# YarnControl_Connect_v1_1.net
KiCad netlist of a schematic drawn in Altium Designer
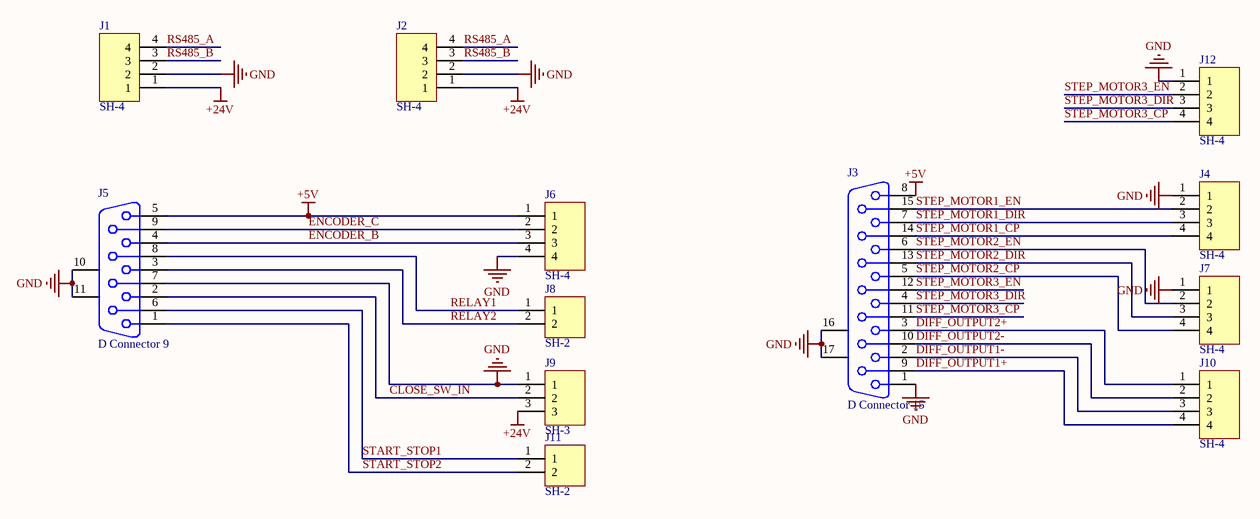
[diagram p0: YarnControl_Connect_v1.1.SchDoc]

(export (version "E")
  (design (tool "Eeschema 10.0.6"))
  (components
    (comp (ref "J1") (value "SH-4") (footprint "PWR") (libsource (lib "") (part "SH-4_1")))
    (comp (ref "J2") (value "SH-4") (footprint "PWR") (libsource (lib "") (part "SH-4_1")))
    (comp (ref "J3")
      (value "D Connector 15")
      (footprint "DSUB1.385-2H15")
      (description "Receptacle Assembly, 15 Position, Right Angle")
      (fields (field (name "PUBLISHER") "Altium Limited"))
      (libsource (lib "Miscellaneous Connectors") (part "D Connector 15"))
    )
    (comp (ref "J4") (value "SH-4") (footprint "PWR") (libsource (lib "Connector") (part "SH-4")))
    (comp (ref "J5")
      (value "D Connector 9")
      (footprint "DSUB1.385-2H9")
      (description "Receptacle Assembly, 9 Position, Right Angle")
      (fields (field (name "PUBLISHER") "Altium Limited"))
      (libsource (lib "Miscellaneous Connectors") (part "D Connector 9"))
    )
    (comp (ref "J6") (value "SH-4") (footprint "PWR") (libsource (lib "Connector") (part "SH-4")))
    (comp (ref "J7") (value "SH-4") (footprint "PWR") (libsource (lib "Connector") (part "SH-4")))
    (comp (ref "J8") (value "SH-2") (footprint "J508-2(1)") (libsource (lib "Connector") (part "SH-2")))
    (comp (ref "J9") (value "SH-3") (footprint "J508-3") (libsource (lib "Connector") (part "SH-3")))
    (comp (ref "J10") (value "SH-4") (footprint "PWR") (libsource (lib "Connector") (part "SH-4")))
    (comp (ref "J11") (value "SH-2") (footprint "J508-2(1)") (libsource (lib "Connector") (part "SH-2")))
    (comp (ref "J12") (value "SH-4") (footprint "PWR") (libsource (lib "Connector") (part "SH-4")))
  )
  (nets
    (net (code "1") (name "+5V") (class "Default")
      (node (ref "J3") (pin "8") (pinfunction "8_8") (pintype "passive"))
      (node (ref "J5") (pin "5") (pinfunction "5_5") (pintype "passive"))
      (node (ref "J6") (pin "1") (pinfunction "1_1") (pintype "passive"))
    )
    (net (code "2") (name "+24V") (class "Default")
      (node (ref "J1") (pin "1") (pinfunction "1_1") (pintype "passive"))
      (node (ref "J2") (pin "1") (pinfunction "1_1") (pintype "passive"))
      (node (ref "J9") (pin "3") (pinfunction "3_3") (pintype "passive"))
    )
    (net (code "3") (name "/CLOSE_SW_IN") (class "Default")
      (node (ref "J5") (pin "2") (pinfunction "2_2") (pintype "passive"))
      (node (ref "J9") (pin "2") (pinfunction "2_2") (pintype "passive"))
    )
    (net (code "4") (name "/DIFF_OUTPUT1+") (class "Default")
      (node (ref "J10") (pin "4") (pinfunction "4_4") (pintype "passive"))
      (node (ref "J3") (pin "9") (pinfunction "9_9") (pintype "passive"))
    )
    (net (code "5") (name "/DIFF_OUTPUT1-") (class "Default")
      (node (ref "J10") (pin "3") (pinfunction "3_3") (pintype "passive"))
      (node (ref "J3") (pin "2") (pinfunction "2_2") (pintype "passive"))
    )
    (net (code "6") (name "/DIFF_OUTPUT2+") (class "Default")
      (node (ref "J10") (pin "1") (pinfunction "1_1") (pintype "passive"))
      (node (ref "J3") (pin "3") (pinfunction "3_3") (pintype "passive"))
    )
    (net (code "7") (name "/DIFF_OUTPUT2-") (class "Default")
      (node (ref "J10") (pin "2") (pinfunction "2_2") (pintype "passive"))
      (node (ref "J3") (pin "10") (pinfunction "10_10") (pintype "passive"))
    )
    (net (code "8") (name "/ENCODER_B") (class "Default")
      (node (ref "J5") (pin "4") (pinfunction "4_4") (pintype "passive"))
      (node (ref "J6") (pin "3") (pinfunction "3_3") (pintype "passive"))
    )
    (net (code "9") (name "/ENCODER_C") (class "Default")
      (node (ref "J5") (pin "9") (pinfunction "9_9") (pintype "passive"))
      (node (ref "J6") (pin "2") (pinfunction "2_2") (pintype "passive"))
    )
    (net (code "10") (name "/RELAY1") (class "Default")
      (node (ref "J5") (pin "8") (pinfunction "8_8") (pintype "passive"))
      (node (ref "J8") (pin "1") (pinfunction "1_1") (pintype "passive"))
    )
    (net (code "11") (name "/RELAY2") (class "Default")
      (node (ref "J5") (pin "3") (pinfunction "3_3") (pintype "passive"))
      (node (ref "J8") (pin "2") (pinfunction "2_2") (pintype "passive"))
    )
    (net (code "12") (name "/RS485_A") (class "Default")
      (node (ref "J1") (pin "4") (pinfunction "4_4") (pintype "passive"))
      (node (ref "J2") (pin "4") (pinfunction "4_4") (pintype "passive"))
    )
    (net (code "13") (name "/RS485_B") (class "Default")
      (node (ref "J1") (pin "3") (pinfunction "3_3") (pintype "passive"))
      (node (ref "J2") (pin "3") (pinfunction "3_3") (pintype "passive"))
    )
    (net (code "14") (name "/START_STOP1") (class "Default")
      (node (ref "J11") (pin "1") (pinfunction "1_1") (pintype "passive"))
      (node (ref "J5") (pin "6") (pinfunction "6_6") (pintype "passive"))
    )
    (net (code "15") (name "/START_STOP2") (class "Default")
      (node (ref "J11") (pin "2") (pinfunction "2_2") (pintype "passive"))
      (node (ref "J5") (pin "1") (pinfunction "1_1") (pintype "passive"))
    )
    (net (code "16") (name "/STEP_MOTOR1_CP") (class "Default")
      (node (ref "J3") (pin "14") (pinfunction "14_14") (pintype "passive"))
      (node (ref "J4") (pin "4") (pinfunction "4_4") (pintype "passive"))
    )
    (net (code "17") (name "/STEP_MOTOR1_DIR") (class "Default")
      (node (ref "J3") (pin "7") (pinfunction "7_7") (pintype "passive"))
      (node (ref "J4") (pin "3") (pinfunction "3_3") (pintype "passive"))
    )
    (net (code "18") (name "/STEP_MOTOR1_EN") (class "Default")
      (node (ref "J3") (pin "15") (pinfunction "15_15") (pintype "passive"))
      (node (ref "J4") (pin "2") (pinfunction "2_2") (pintype "passive"))
    )
    (net (code "19") (name "/STEP_MOTOR2_CP") (class "Default")
      (node (ref "J3") (pin "5") (pinfunction "5_5") (pintype "passive"))
      (node (ref "J7") (pin "4") (pinfunction "4_4") (pintype "passive"))
    )
    (net (code "20") (name "/STEP_MOTOR2_DIR") (class "Default")
      (node (ref "J3") (pin "13") (pinfunction "13_13") (pintype "passive"))
      (node (ref "J7") (pin "3") (pinfunction "3_3") (pintype "passive"))
    )
    (net (code "21") (name "/STEP_MOTOR2_EN") (class "Default")
      (node (ref "J3") (pin "6") (pinfunction "6_6") (pintype "passive"))
      (node (ref "J7") (pin "2") (pinfunction "2_2") (pintype "passive"))
    )
    (net (code "22") (name "/STEP_MOTOR3_CP") (class "Default")
      (node (ref "J12") (pin "4") (pinfunction "4_4") (pintype "passive"))
      (node (ref "J3") (pin "11") (pinfunction "11_11") (pintype "passive"))
    )
    (net (code "23") (name "/STEP_MOTOR3_DIR") (class "Default")
      (node (ref "J12") (pin "3") (pinfunction "3_3") (pintype "passive"))
      (node (ref "J3") (pin "4") (pinfunction "4_4") (pintype "passive"))
    )
    (net (code "24") (name "/STEP_MOTOR3_EN") (class "Default")
      (node (ref "J12") (pin "2") (pinfunction "2_2") (pintype "passive"))
      (node (ref "J3") (pin "12") (pinfunction "12_12") (pintype "passive"))
    )
    (net (code "25") (name "GND") (class "Default")
      (node (ref "J1") (pin "2") (pinfunction "2_2") (pintype "passive"))
      (node (ref "J12") (pin "1") (pinfunction "1_1") (pintype "passive"))
      (node (ref "J2") (pin "2") (pinfunction "2_2") (pintype "passive"))
      (node (ref "J3") (pin "1") (pinfunction "1_1") (pintype "passive"))
      (node (ref "J3") (pin "16") (pinfunction "MH1_16") (pintype "passive"))
      (node (ref "J3") (pin "17") (pinfunction "MH2_17") (pintype "passive"))
      (node (ref "J4") (pin "1") (pinfunction "1_1") (pintype "passive"))
      (node (ref "J5") (pin "10") (pinfunction "MH1_10") (pintype "passive"))
      (node (ref "J5") (pin "11") (pinfunction "MH2_11") (pintype "passive"))
      (node (ref "J5") (pin "7") (pinfunction "7_7") (pintype "passive"))
      (node (ref "J6") (pin "4") (pinfunction "4_4") (pintype "passive"))
      (node (ref "J7") (pin "1") (pinfunction "1_1") (pintype "passive"))
      (node (ref "J9") (pin "1") (pinfunction "1_1") (pintype "passive"))
    )
  )
)
